# Top.net
KiCad netlist of a schematic drawn in Altium Designer
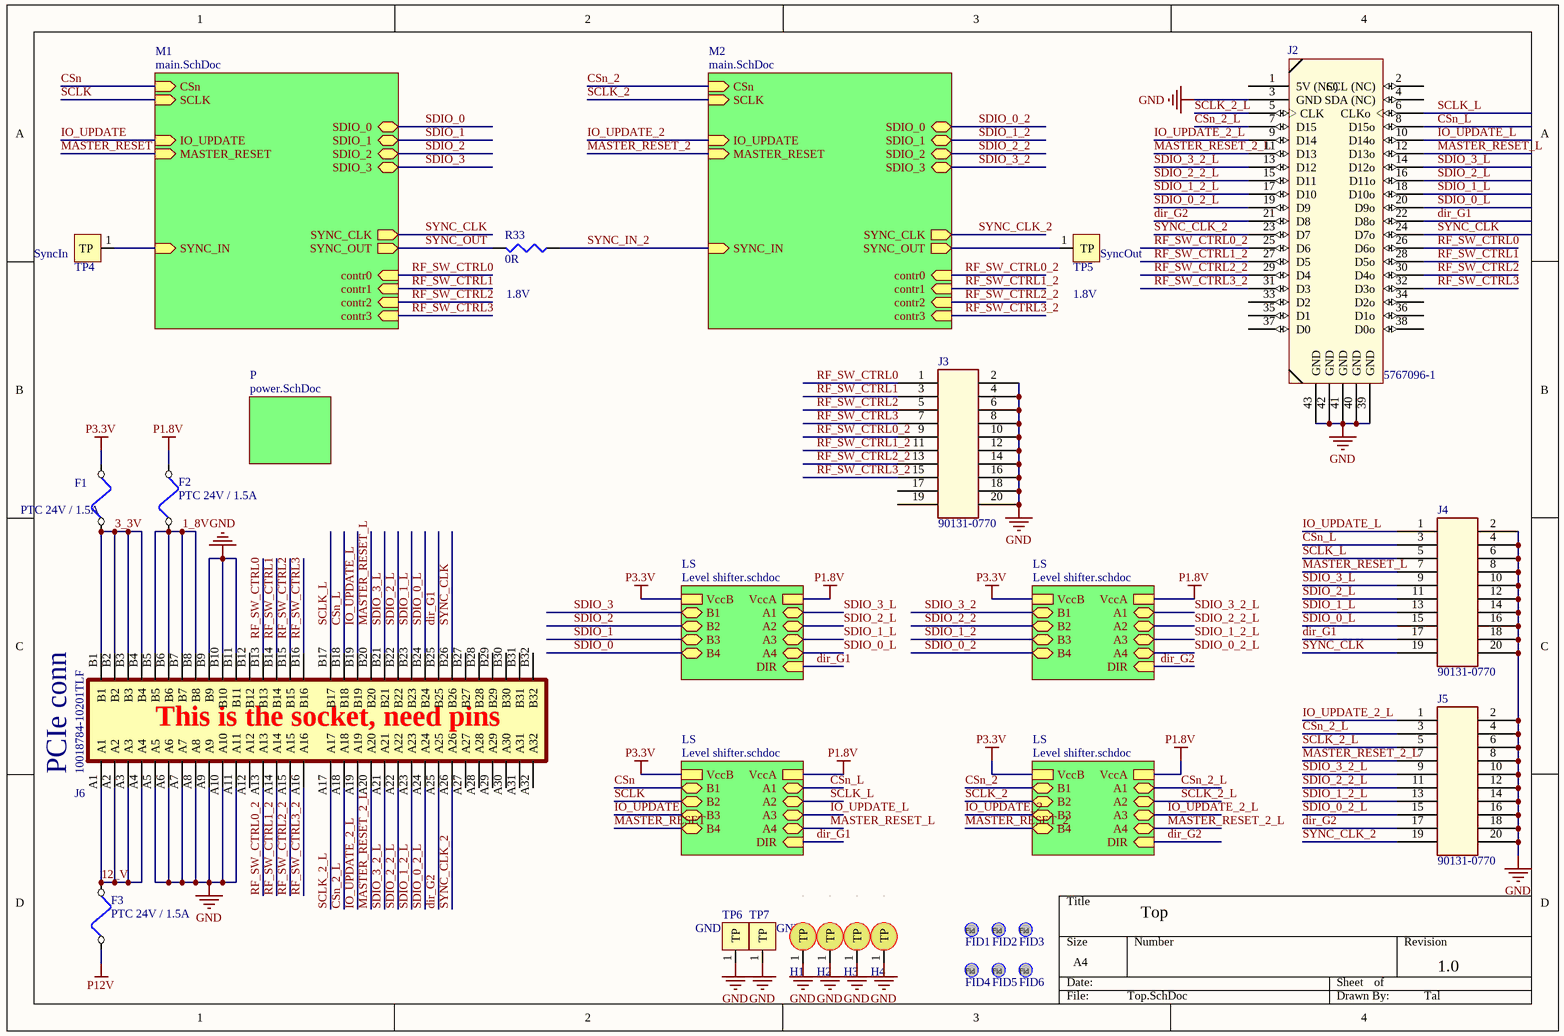
[diagram p0: Top.SchDoc]

(export (version "E")
  (design (tool "Eeschema 10.0.6"))
  (components
    (comp (ref "F1")
      (value "PTC 24V / 1.5A")
      (footprint "1812_F")
      (description "FUSE PTC 24V 1.5A POLYFUSE 1812")
      (fields
        (field (name "MANUFACTURER") "Littelfuse Inc")
        (field (name "MANUFACTURER PART NUMBER") "1812L150/24MR")
      )
      (libsource (lib "DPB_spliter") (part "1812L150/24MR"))
    )
    (comp (ref "F2")
      (value "PTC 24V / 1.5A")
      (footprint "1812_F")
      (description "FUSE PTC 24V 1.5A POLYFUSE 1812")
      (fields
        (field (name "MANUFACTURER") "Littelfuse Inc")
        (field (name "MANUFACTURER PART NUMBER") "1812L150/24MR")
      )
      (libsource (lib "DPB_spliter") (part "1812L150/24MR"))
    )
    (comp (ref "F3")
      (value "PTC 24V / 1.5A")
      (footprint "1812_F")
      (description "FUSE PTC 24V 1.5A POLYFUSE 1812")
      (fields
        (field (name "MANUFACTURER") "Littelfuse Inc")
        (field (name "MANUFACTURER PART NUMBER") "1812L150/24MR")
      )
      (libsource (lib "DPB_spliter") (part "1812L150/24MR"))
    )
    (comp (ref "FID1")
      (value "Fiducial")
      (footprint "Fiducial")
      (libsource (lib "DDS_PCB") (part "Fiducial"))
    )
    (comp (ref "FID2")
      (value "Fiducial")
      (footprint "Fiducial")
      (libsource (lib "DDS_PCB") (part "Fiducial"))
    )
    (comp (ref "FID3")
      (value "Fiducial")
      (footprint "Fiducial")
      (libsource (lib "DDS_PCB") (part "Fiducial"))
    )
    (comp (ref "FID4")
      (value "Fiducial")
      (footprint "Fiducial")
      (libsource (lib "DDS_PCB") (part "Fiducial"))
    )
    (comp (ref "FID5")
      (value "Fiducial")
      (footprint "Fiducial")
      (libsource (lib "DDS_PCB") (part "Fiducial"))
    )
    (comp (ref "FID6")
      (value "Fiducial")
      (footprint "Fiducial")
      (libsource (lib "DDS_PCB") (part "Fiducial"))
    )
    (comp (ref "H1")
      (value "Hole 3mm")
      (footprint "hole 3mm")
      (description "hole 3mm")
      (libsource (lib "L_SCH_Misc") (part "Hole 3mm"))
    )
    (comp (ref "H2")
      (value "Hole 3mm")
      (footprint "hole 3mm")
      (description "hole 3mm")
      (libsource (lib "L_SCH_Misc") (part "Hole 3mm"))
    )
    (comp (ref "H3")
      (value "Hole 3mm")
      (footprint "hole 3mm")
      (description "hole 3mm")
      (libsource (lib "L_SCH_Misc") (part "Hole 3mm"))
    )
    (comp (ref "H4")
      (value "Hole 3mm")
      (footprint "hole 3mm")
      (description "hole 3mm")
      (libsource (lib "L_SCH_Misc") (part "Hole 3mm"))
    )
    (comp (ref "J2")
      (value "5767096-1")
      (footprint "MICTOR-38_PIN")
      (description "CONN MICTOR 38POS .025 VERT SMD")
      (fields
        (field (name "MANUFACTURER") "TE Connectivity")
        (field (name "MANUFACTURER PART NUMBER") "5767096-1")
      )
      (libsource (lib "L_SCH_J_Z") (part "5767096-1"))
    )
    (comp (ref "J3")
      (value "90131-0770")
      (footprint "HEADER_10x2")
      (description "CONN HEADER 20 TH")
      (fields
        (field (name "MANUFACTURER") "Molex Connector Corporation")
        (field (name "MANUFACTURER PART NUMBER") "90131-0770")
      )
      (libsource (lib "L_SCH_J_Z") (part "90131-0770"))
    )
    (comp (ref "J4")
      (value "90131-0770")
      (footprint "HEADER_10x2")
      (description "CONN HEADER 20 TH")
      (fields
        (field (name "MANUFACTURER") "Molex Connector Corporation")
        (field (name "MANUFACTURER PART NUMBER") "90131-0770")
      )
      (libsource (lib "L_SCH_J_Z") (part "90131-0770"))
    )
    (comp (ref "J5")
      (value "90131-0770")
      (footprint "HEADER_10x2")
      (description "CONN HEADER 20 TH")
      (fields
        (field (name "MANUFACTURER") "Molex Connector Corporation")
        (field (name "MANUFACTURER PART NUMBER") "90131-0770")
      )
      (libsource (lib "L_SCH_J_Z") (part "90131-0770"))
    )
    (comp (ref "J6")
      (value "10018784-10201TLF")
      (footprint "PCIE_8LANE_EDGE")
      (description "64 Position Female Connector PCI Expressâ„¢ Gold 0.039 _1.00mm_ Black")
      (fields (field (name "MF") "Amphenol ICC"))
      (libsource (lib "10018784-10201TLF") (part "10018784-10201TLF"))
    )
    (comp (ref "R33")
      (value "0R")
      (footprint "R0402")
      (description "RES 0 OHM 1/10W 1% 0402 SMD")
      (fields
        (field (name "MANUFACTURER PART NUMBER") "ERJ-2RKF1000X")
        (field (name "MANUFACTURER") "Panasonic Electronic Components")
      )
      (libsource (lib "L_SCH_R") (part "RES 100 OHM 1/10W 1% 0402 SMD"))
    )
    (comp (ref "TP4")
      (value "SyncIn")
      (footprint "Landa_PCB:TP_2x1.8")
      (description "TP PC MINIATURE SMT")
      (fields
        (field (name "MANUFACTURER") "Keystone Electronics")
        (field (name "MANUFACTURER PART NUMBER") "5015")
      )
      (libsource (lib "") (part "TP mini_2_1"))
    )
    (comp (ref "TP5")
      (value "SyncOut")
      (footprint "Landa_PCB:TP_2x1.8")
      (description "TP PC MINIATURE SMT")
      (fields
        (field (name "MANUFACTURER") "Keystone Electronics")
        (field (name "MANUFACTURER PART NUMBER") "5015")
      )
      (libsource (lib "") (part "TP mini_2_2"))
    )
    (comp (ref "TP6")
      (value "GND")
      (footprint "Landa_PCB:TP_2x1.8")
      (description "TP PC MINIATURE SMT")
      (fields
        (field (name "MANUFACTURER") "Keystone Electronics")
        (field (name "MANUFACTURER PART NUMBER") "5015")
      )
      (libsource (lib "DPB_spliter") (part "TP mini_2"))
    )
    (comp (ref "TP7")
      (value "GND")
      (footprint "Landa_PCB:TP_2x1.8")
      (description "TP PC MINIATURE SMT")
      (fields
        (field (name "MANUFACTURER") "Keystone Electronics")
        (field (name "MANUFACTURER PART NUMBER") "5015")
      )
      (libsource (lib "DPB_spliter") (part "TP mini_1"))
    )
  )
  (nets
    (net (code "1") (name "/1_8V") (class "Default")
      (node (ref "F2") (pin "1") (pinfunction "1_1") (pintype "passive"))
      (node (ref "J6") (pin "B5") (pinfunction "B5_B5") (pintype "passive"))
      (node (ref "J6") (pin "B6") (pinfunction "B6_B6") (pintype "passive"))
      (node (ref "J6") (pin "B7") (pinfunction "B7_B7") (pintype "passive"))
      (node (ref "J6") (pin "B8") (pinfunction "B8_B8") (pintype "passive"))
    )
    (net (code "2") (name "/3_3V") (class "Default")
      (node (ref "F1") (pin "1") (pinfunction "1_1") (pintype "passive"))
      (node (ref "J6") (pin "B1") (pinfunction "B1_B1") (pintype "passive"))
      (node (ref "J6") (pin "B2") (pinfunction "B2_B2") (pintype "passive"))
      (node (ref "J6") (pin "B3") (pinfunction "B3_B3") (pintype "passive"))
      (node (ref "J6") (pin "B4") (pinfunction "B4_B4") (pintype "passive"))
    )
    (net (code "3") (name "/12_V") (class "Default")
      (node (ref "F3") (pin "2") (pinfunction "2_2") (pintype "passive"))
      (node (ref "J6") (pin "A1") (pinfunction "A1_A1") (pintype "passive"))
      (node (ref "J6") (pin "A2") (pinfunction "A2_A2") (pintype "passive"))
      (node (ref "J6") (pin "A3") (pinfunction "A3_A3") (pintype "passive"))
      (node (ref "J6") (pin "A4") (pinfunction "A4_A4") (pintype "passive"))
    )
    (net (code "6") (name "/CSn_2_L") (class "Default")
      (node (ref "J2") (pin "7") (pinfunction "D15_7") (pintype "bidirectional"))
      (node (ref "J5") (pin "3") (pinfunction "3_3") (pintype "passive"))
      (node (ref "J6") (pin "A18") (pinfunction "A18_A18") (pintype "passive"))
    )
    (net (code "7") (name "/CSn_L") (class "Default")
      (node (ref "J2") (pin "8") (pinfunction "D15o_8") (pintype "bidirectional"))
      (node (ref "J4") (pin "3") (pinfunction "3_3") (pintype "passive"))
      (node (ref "J6") (pin "B18") (pinfunction "B18_B18") (pintype "passive"))
    )
    (net (code "10") (name "/IO_UPDATE_2_L") (class "Default")
      (node (ref "J2") (pin "9") (pinfunction "D14_9") (pintype "bidirectional"))
      (node (ref "J5") (pin "1") (pinfunction "1_1") (pintype "passive"))
      (node (ref "J6") (pin "A19") (pinfunction "A19_A19") (pintype "passive"))
    )
    (net (code "11") (name "/IO_UPDATE_L") (class "Default")
      (node (ref "J2") (pin "10") (pinfunction "D14o_10") (pintype "bidirectional"))
      (node (ref "J4") (pin "1") (pinfunction "1_1") (pintype "passive"))
      (node (ref "J6") (pin "B19") (pinfunction "B19_B19") (pintype "passive"))
    )
    (net (code "14") (name "/MASTER_RESET_2_L") (class "Default")
      (node (ref "J2") (pin "11") (pinfunction "D13_11") (pintype "bidirectional"))
      (node (ref "J5") (pin "7") (pinfunction "7_7") (pintype "passive"))
      (node (ref "J6") (pin "A20") (pinfunction "A20_A20") (pintype "passive"))
    )
    (net (code "15") (name "/MASTER_RESET_L") (class "Default")
      (node (ref "J2") (pin "12") (pinfunction "D13o_12") (pintype "bidirectional"))
      (node (ref "J4") (pin "7") (pinfunction "7_7") (pintype "passive"))
      (node (ref "J6") (pin "B20") (pinfunction "B20_B20") (pintype "passive"))
    )
    (net (code "16") (name "/RF_SW_CTRL0") (class "Default")
      (node (ref "J2") (pin "26") (pinfunction "D6o_26") (pintype "bidirectional"))
      (node (ref "J3") (pin "1") (pinfunction "1_1") (pintype "passive"))
      (node (ref "J6") (pin "B13") (pinfunction "B13_B13") (pintype "passive"))
    )
    (net (code "17") (name "/RF_SW_CTRL0_2") (class "Default")
      (node (ref "J2") (pin "25") (pinfunction "D6_25") (pintype "bidirectional"))
      (node (ref "J3") (pin "9") (pinfunction "9_9") (pintype "passive"))
      (node (ref "J6") (pin "A13") (pinfunction "A13_A13") (pintype "passive"))
    )
    (net (code "18") (name "/RF_SW_CTRL1") (class "Default")
      (node (ref "J2") (pin "28") (pinfunction "D5o_28") (pintype "bidirectional"))
      (node (ref "J3") (pin "3") (pinfunction "3_3") (pintype "passive"))
      (node (ref "J6") (pin "B14") (pinfunction "B14_B14") (pintype "passive"))
    )
    (net (code "19") (name "/RF_SW_CTRL1_2") (class "Default")
      (node (ref "J2") (pin "27") (pinfunction "D5_27") (pintype "bidirectional"))
      (node (ref "J3") (pin "11") (pinfunction "11_11") (pintype "passive"))
      (node (ref "J6") (pin "A14") (pinfunction "A14_A14") (pintype "passive"))
    )
    (net (code "20") (name "/RF_SW_CTRL2") (class "Default")
      (node (ref "J2") (pin "30") (pinfunction "D4o_30") (pintype "bidirectional"))
      (node (ref "J3") (pin "5") (pinfunction "5_5") (pintype "passive"))
      (node (ref "J6") (pin "B15") (pinfunction "B15_B15") (pintype "passive"))
    )
    (net (code "21") (name "/RF_SW_CTRL2_2") (class "Default")
      (node (ref "J2") (pin "29") (pinfunction "D4_29") (pintype "bidirectional"))
      (node (ref "J3") (pin "13") (pinfunction "13_13") (pintype "passive"))
      (node (ref "J6") (pin "A15") (pinfunction "A15_A15") (pintype "passive"))
    )
    (net (code "22") (name "/RF_SW_CTRL3") (class "Default")
      (node (ref "J2") (pin "32") (pinfunction "D3o_32") (pintype "bidirectional"))
      (node (ref "J3") (pin "7") (pinfunction "7_7") (pintype "passive"))
      (node (ref "J6") (pin "B16") (pinfunction "B16_B16") (pintype "passive"))
    )
    (net (code "23") (name "/RF_SW_CTRL3_2") (class "Default")
      (node (ref "J2") (pin "31") (pinfunction "D3_31") (pintype "bidirectional"))
      (node (ref "J3") (pin "15") (pinfunction "15_15") (pintype "passive"))
      (node (ref "J6") (pin "A16") (pinfunction "A16_A16") (pintype "passive"))
    )
    (net (code "26") (name "/SCLK_2_L") (class "Default")
      (node (ref "J2") (pin "5") (pinfunction "CLK_5") (pintype "bidirectional"))
      (node (ref "J5") (pin "5") (pinfunction "5_5") (pintype "passive"))
      (node (ref "J6") (pin "A17") (pinfunction "A17_A17") (pintype "passive"))
    )
    (net (code "27") (name "/SCLK_L") (class "Default")
      (node (ref "J2") (pin "6") (pinfunction "CLKo_6") (pintype "bidirectional"))
      (node (ref "J4") (pin "5") (pinfunction "5_5") (pintype "passive"))
      (node (ref "J6") (pin "B17") (pinfunction "B17_B17") (pintype "passive"))
    )
    (net (code "30") (name "/SDIO_0_2_L") (class "Default")
      (node (ref "J2") (pin "19") (pinfunction "D9_19") (pintype "bidirectional"))
      (node (ref "J5") (pin "15") (pinfunction "15_15") (pintype "passive"))
      (node (ref "J6") (pin "A24") (pinfunction "A24_A24") (pintype "passive"))
    )
    (net (code "31") (name "/SDIO_0_L") (class "Default")
      (node (ref "J2") (pin "20") (pinfunction "D9o_20") (pintype "bidirectional"))
      (node (ref "J4") (pin "15") (pinfunction "15_15") (pintype "passive"))
      (node (ref "J6") (pin "B24") (pinfunction "B24_B24") (pintype "passive"))
    )
    (net (code "34") (name "/SDIO_1_2_L") (class "Default")
      (node (ref "J2") (pin "17") (pinfunction "D10_17") (pintype "bidirectional"))
      (node (ref "J5") (pin "13") (pinfunction "13_13") (pintype "passive"))
      (node (ref "J6") (pin "A23") (pinfunction "A23_A23") (pintype "passive"))
    )
    (net (code "35") (name "/SDIO_1_L") (class "Default")
      (node (ref "J2") (pin "18") (pinfunction "D10o_18") (pintype "bidirectional"))
      (node (ref "J4") (pin "13") (pinfunction "13_13") (pintype "passive"))
      (node (ref "J6") (pin "B23") (pinfunction "B23_B23") (pintype "passive"))
    )
    (net (code "38") (name "/SDIO_2_2_L") (class "Default")
      (node (ref "J2") (pin "15") (pinfunction "D11_15") (pintype "bidirectional"))
      (node (ref "J5") (pin "11") (pinfunction "11_11") (pintype "passive"))
      (node (ref "J6") (pin "A22") (pinfunction "A22_A22") (pintype "passive"))
    )
    (net (code "39") (name "/SDIO_2_L") (class "Default")
      (node (ref "J2") (pin "16") (pinfunction "D11o_16") (pintype "bidirectional"))
      (node (ref "J4") (pin "11") (pinfunction "11_11") (pintype "passive"))
      (node (ref "J6") (pin "B22") (pinfunction "B22_B22") (pintype "passive"))
    )
    (net (code "42") (name "/SDIO_3_2_L") (class "Default")
      (node (ref "J2") (pin "13") (pinfunction "D12_13") (pintype "bidirectional"))
      (node (ref "J5") (pin "9") (pinfunction "9_9") (pintype "passive"))
      (node (ref "J6") (pin "A21") (pinfunction "A21_A21") (pintype "passive"))
    )
    (net (code "43") (name "/SDIO_3_L") (class "Default")
      (node (ref "J2") (pin "14") (pinfunction "D12o_14") (pintype "bidirectional"))
      (node (ref "J4") (pin "9") (pinfunction "9_9") (pintype "passive"))
      (node (ref "J6") (pin "B21") (pinfunction "B21_B21") (pintype "passive"))
    )
    (net (code "44") (name "/SYNC_CLK") (class "Default")
      (node (ref "J2") (pin "24") (pinfunction "D7o_24") (pintype "bidirectional"))
      (node (ref "J4") (pin "19") (pinfunction "19_19") (pintype "passive"))
      (node (ref "J6") (pin "B26") (pinfunction "B26_B26") (pintype "passive"))
    )
    (net (code "45") (name "/SYNC_CLK_2") (class "Default")
      (node (ref "J2") (pin "23") (pinfunction "D7_23") (pintype "bidirectional"))
      (node (ref "J5") (pin "19") (pinfunction "19_19") (pintype "passive"))
      (node (ref "J6") (pin "A26") (pinfunction "A26_A26") (pintype "passive"))
    )
    (net (code "46") (name "/SYNC_IN") (class "Default")
      (node (ref "TP4") (pin "1") (pinfunction "TP_1") (pintype "passive"))
    )
    (net (code "47") (name "/SYNC_IN_2") (class "Default")
      (node (ref "R33") (pin "1") (pinfunction "1_1") (pintype "passive"))
    )
    (net (code "48") (name "/SYNC_OUT") (class "Default")
      (node (ref "R33") (pin "2") (pinfunction "2_2") (pintype "passive"))
    )
    (net (code "49") (name "/SYNC_OUT_1") (class "Default")
      (node (ref "TP5") (pin "1") (pinfunction "TP_1") (pintype "passive"))
    )
    (net (code "50") (name "/dir_G1") (class "Default")
      (node (ref "J2") (pin "22") (pinfunction "D8o_22") (pintype "bidirectional"))
      (node (ref "J4") (pin "17") (pinfunction "17_17") (pintype "passive"))
      (node (ref "J6") (pin "B25") (pinfunction "B25_B25") (pintype "passive"))
    )
    (net (code "51") (name "/dir_G2") (class "Default")
      (node (ref "J2") (pin "21") (pinfunction "D8_21") (pintype "bidirectional"))
      (node (ref "J5") (pin "17") (pinfunction "17_17") (pintype "passive"))
      (node (ref "J6") (pin "A25") (pinfunction "A25_A25") (pintype "passive"))
    )
    (net (code "52") (name "GND") (class "Default")
      (node (ref "H1") (pin "1") (pinfunction "TP_1") (pintype "passive"))
      (node (ref "H2") (pin "1") (pinfunction "TP_1") (pintype "passive"))
      (node (ref "H3") (pin "1") (pinfunction "TP_1") (pintype "passive"))
      (node (ref "H4") (pin "1") (pinfunction "TP_1") (pintype "passive"))
      (node (ref "J2") (pin "3") (pinfunction "GND_3") (pintype "power_in"))
      (node (ref "J2") (pin "39") (pinfunction "GND_39") (pintype "power_in"))
      (node (ref "J2") (pin "40") (pinfunction "GND_40") (pintype "power_in"))
      (node (ref "J2") (pin "41") (pinfunction "GND_41") (pintype "power_in"))
      (node (ref "J2") (pin "42") (pinfunction "GND_42") (pintype "power_in"))
      (node (ref "J2") (pin "43") (pinfunction "GND_43") (pintype "power_in"))
      (node (ref "J3") (pin "10") (pinfunction "10_10") (pintype "passive"))
      (node (ref "J3") (pin "12") (pinfunction "12_12") (pintype "passive"))
      (node (ref "J3") (pin "14") (pinfunction "14_14") (pintype "passive"))
      (node (ref "J3") (pin "16") (pinfunction "16_16") (pintype "passive"))
      (node (ref "J3") (pin "18") (pinfunction "18_18") (pintype "passive"))
      (node (ref "J3") (pin "2") (pinfunction "2_2") (pintype "passive"))
      (node (ref "J3") (pin "20") (pinfunction "20_20") (pintype "passive"))
      (node (ref "J3") (pin "4") (pinfunction "4_4") (pintype "passive"))
      (node (ref "J3") (pin "6") (pinfunction "6_6") (pintype "passive"))
      (node (ref "J3") (pin "8") (pinfunction "8_8") (pintype "passive"))
      (node (ref "J4") (pin "10") (pinfunction "10_10") (pintype "passive"))
      (node (ref "J4") (pin "12") (pinfunction "12_12") (pintype "passive"))
      (node (ref "J4") (pin "14") (pinfunction "14_14") (pintype "passive"))
      (node (ref "J4") (pin "16") (pinfunction "16_16") (pintype "passive"))
      (node (ref "J4") (pin "18") (pinfunction "18_18") (pintype "passive"))
      (node (ref "J4") (pin "2") (pinfunction "2_2") (pintype "passive"))
      (node (ref "J4") (pin "20") (pinfunction "20_20") (pintype "passive"))
      (node (ref "J4") (pin "4") (pinfunction "4_4") (pintype "passive"))
      (node (ref "J4") (pin "6") (pinfunction "6_6") (pintype "passive"))
      (node (ref "J4") (pin "8") (pinfunction "8_8") (pintype "passive"))
      (node (ref "J5") (pin "10") (pinfunction "10_10") (pintype "passive"))
      (node (ref "J5") (pin "12") (pinfunction "12_12") (pintype "passive"))
      (node (ref "J5") (pin "14") (pinfunction "14_14") (pintype "passive"))
      (node (ref "J5") (pin "16") (pinfunction "16_16") (pintype "passive"))
      (node (ref "J5") (pin "18") (pinfunction "18_18") (pintype "passive"))
      (node (ref "J5") (pin "2") (pinfunction "2_2") (pintype "passive"))
      (node (ref "J5") (pin "20") (pinfunction "20_20") (pintype "passive"))
      (node (ref "J5") (pin "4") (pinfunction "4_4") (pintype "passive"))
      (node (ref "J5") (pin "6") (pinfunction "6_6") (pintype "passive"))
      (node (ref "J5") (pin "8") (pinfunction "8_8") (pintype "passive"))
      (node (ref "J6") (pin "A10") (pinfunction "A10_A10") (pintype "passive"))
      (node (ref "J6") (pin "A11") (pinfunction "A11_A11") (pintype "passive"))
      (node (ref "J6") (pin "A5") (pinfunction "A5_A5") (pintype "passive"))
      (node (ref "J6") (pin "A6") (pinfunction "A6_A6") (pintype "passive"))
      (node (ref "J6") (pin "A7") (pinfunction "A7_A7") (pintype "passive"))
      (node (ref "J6") (pin "A8") (pinfunction "A8_A8") (pintype "passive"))
      (node (ref "J6") (pin "A9") (pinfunction "A9_A9") (pintype "passive"))
      (node (ref "J6") (pin "B10") (pinfunction "B10_B10") (pintype "passive"))
      (node (ref "J6") (pin "B11") (pinfunction "B11_B11") (pintype "passive"))
      (node (ref "J6") (pin "B9") (pinfunction "B9_B9") (pintype "passive"))
      (node (ref "TP6") (pin "1") (pinfunction "TP_1") (pintype "passive"))
      (node (ref "TP7") (pin "1") (pinfunction "TP_1") (pintype "passive"))
    )
    (net (code "53") (name "P1.8V") (class "Default")
      (node (ref "F2") (pin "2") (pinfunction "2_2") (pintype "passive"))
    )
    (net (code "54") (name "P3.3V") (class "Default")
      (node (ref "F1") (pin "2") (pinfunction "2_2") (pintype "passive"))
    )
    (net (code "55") (name "P12V") (class "Default")
      (node (ref "F3") (pin "1") (pinfunction "1_1") (pintype "passive"))
    )
    (net (code "56") (name "unconnected-(J2-5V_(NC)-Pad1)") (class "Default")
      (node (ref "J2") (pin "1") (pinfunction "5V_(NC)_1") (pintype "power_in"))
    )
    (net (code "57") (name "unconnected-(J2-D0-Pad37)") (class "Default")
      (node (ref "J2") (pin "37") (pinfunction "D0_37") (pintype "bidirectional"))
    )
    (net (code "58") (name "unconnected-(J2-D0o-Pad38)") (class "Default")
      (node (ref "J2") (pin "38") (pinfunction "D0o_38") (pintype "bidirectional"))
    )
    (net (code "59") (name "unconnected-(J2-D1-Pad35)") (class "Default")
      (node (ref "J2") (pin "35") (pinfunction "D1_35") (pintype "bidirectional"))
    )
    (net (code "60") (name "unconnected-(J2-D1o-Pad36)") (class "Default")
      (node (ref "J2") (pin "36") (pinfunction "D1o_36") (pintype "bidirectional"))
    )
    (net (code "61") (name "unconnected-(J2-D2-Pad33)") (class "Default")
      (node (ref "J2") (pin "33") (pinfunction "D2_33") (pintype "bidirectional"))
    )
    (net (code "62") (name "unconnected-(J2-D2o-Pad34)") (class "Default")
      (node (ref "J2") (pin "34") (pinfunction "D2o_34") (pintype "bidirectional"))
    )
    (net (code "63") (name "unconnected-(J2-SCL_(NC)-Pad2)") (class "Default")
      (node (ref "J2") (pin "2") (pinfunction "SCL_(NC)_2") (pintype "bidirectional"))
    )
    (net (code "64") (name "unconnected-(J2-SDA_(NC)-Pad4)") (class "Default")
      (node (ref "J2") (pin "4") (pinfunction "SDA_(NC)_4") (pintype "bidirectional"))
    )
    (net (code "65") (name "unconnected-(J3-Pad17)") (class "Default")
      (node (ref "J3") (pin "17") (pinfunction "17_17") (pintype "passive"))
    )
    (net (code "66") (name "unconnected-(J3-Pad19)") (class "Default")
      (node (ref "J3") (pin "19") (pinfunction "19_19") (pintype "passive"))
    )
    (net (code "67") (name "unconnected-(J6-PadA12)") (class "Default")
      (node (ref "J6") (pin "A12") (pinfunction "A12_A12") (pintype "passive"))
    )
    (net (code "68") (name "unconnected-(J6-PadA27)") (class "Default")
      (node (ref "J6") (pin "A27") (pinfunction "A27_A27") (pintype "passive"))
    )
    (net (code "69") (name "unconnected-(J6-PadA28)") (class "Default")
      (node (ref "J6") (pin "A28") (pinfunction "A28_A28") (pintype "passive"))
    )
    (net (code "70") (name "unconnected-(J6-PadA29)") (class "Default")
      (node (ref "J6") (pin "A29") (pinfunction "A29_A29") (pintype "passive"))
    )
    (net (code "71") (name "unconnected-(J6-PadA30)") (class "Default")
      (node (ref "J6") (pin "A30") (pinfunction "A30_A30") (pintype "passive"))
    )
    (net (code "72") (name "unconnected-(J6-PadA31)") (class "Default")
      (node (ref "J6") (pin "A31") (pinfunction "A31_A31") (pintype "passive"))
    )
    (net (code "73") (name "unconnected-(J6-PadA32)") (class "Default")
      (node (ref "J6") (pin "A32") (pinfunction "A32_A32") (pintype "passive"))
    )
    (net (code "74") (name "unconnected-(J6-PadB12)") (class "Default")
      (node (ref "J6") (pin "B12") (pinfunction "B12_B12") (pintype "passive"))
    )
    (net (code "75") (name "unconnected-(J6-PadB27)") (class "Default")
      (node (ref "J6") (pin "B27") (pinfunction "B27_B27") (pintype "passive"))
    )
    (net (code "76") (name "unconnected-(J6-PadB28)") (class "Default")
      (node (ref "J6") (pin "B28") (pinfunction "B28_B28") (pintype "passive"))
    )
    (net (code "77") (name "unconnected-(J6-PadB29)") (class "Default")
      (node (ref "J6") (pin "B29") (pinfunction "B29_B29") (pintype "passive"))
    )
    (net (code "78") (name "unconnected-(J6-PadB30)") (class "Default")
      (node (ref "J6") (pin "B30") (pinfunction "B30_B30") (pintype "passive"))
    )
    (net (code "79") (name "unconnected-(J6-PadB31)") (class "Default")
      (node (ref "J6") (pin "B31") (pinfunction "B31_B31") (pintype "passive"))
    )
    (net (code "80") (name "unconnected-(J6-PadB32)") (class "Default")
      (node (ref "J6") (pin "B32") (pinfunction "B32_B32") (pintype "passive"))
    )
  )
)
